# schematic.net
KiCad netlist of a schematic drawn in EasyEDA
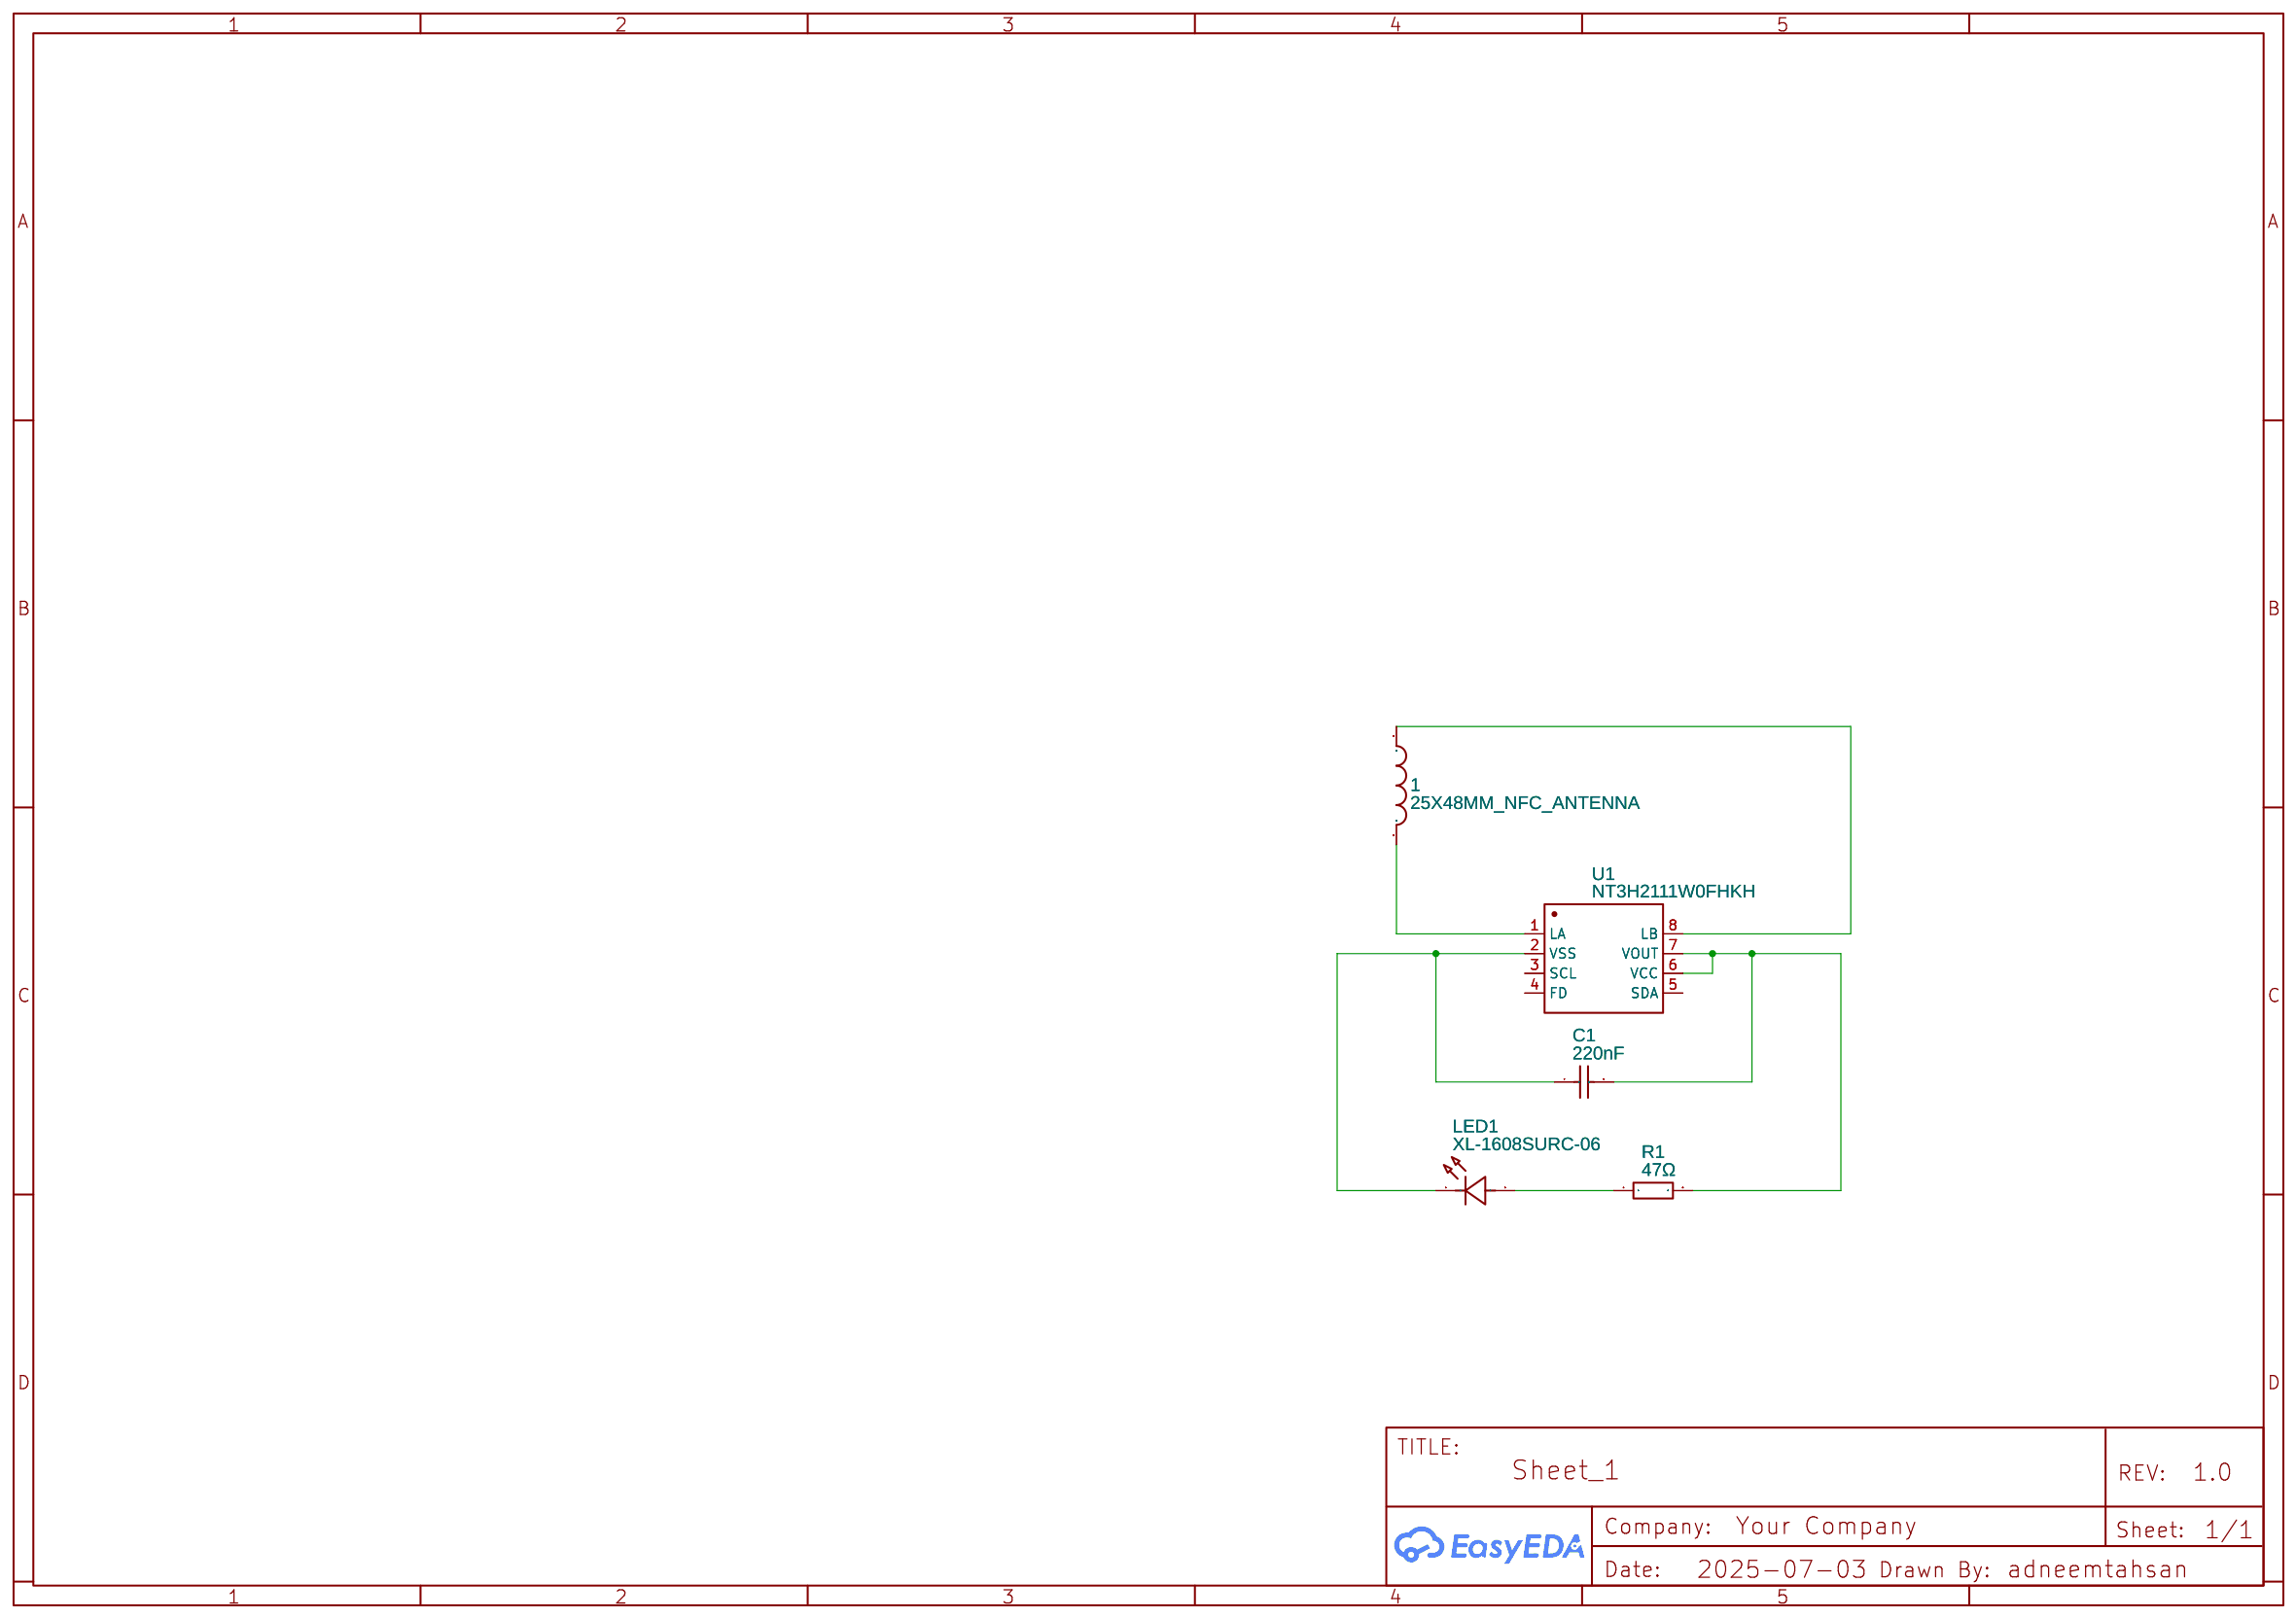
[diagram p0: schematic sheet]

(export (version "E")
  (design (tool "Eeschema 10.0.6"))
  (components
    (comp (ref "1") (value "25X48MM_NFC_ANTENNA") (libsource (lib "") (part "25X48MM_NFC_ANTENNA")))
    (comp (ref "C1")
      (value "220nF")
      (fields
        (field (name "Manufacturer Part") "CL10B224KA8NNNC")
        (field (name "Manufacturer") "SAMSUNG(三星)")
      )
      (libsource (lib "") (part "CL10B224KA8NNNC"))
    )
    (comp (ref "LED1")
      (value "XL-1608SURC-06")
      (fields (field (name "Manufacturer") "XINGLIGHT(成兴光)"))
      (libsource (lib "") (part "XL-1608SURC-06"))
    )
    (comp (ref "R1")
      (value "47Ω")
      (fields
        (field (name "Manufacturer Part") "0603WAF470JT5E")
        (field (name "Manufacturer") "UNI-ROYAL(厚声)")
      )
      (libsource (lib "") (part "0603WAF470JT5E"))
    )
    (comp (ref "U1")
      (value "NT3H2111W0FHKH")
      (fields (field (name "Manufacturer") "NXP(恩智浦)"))
      (libsource (lib "") (part "NT3H2111W0FHKH"))
    )
  )
  (nets
    (net (code "1") (name "Net-(LED1-A)") (class "Default")
      (node (ref "LED1") (pin "2") (pinfunction "A_2") (pintype "unspecified"))
      (node (ref "R1") (pin "1") (pinfunction "1_1") (pintype "input"))
    )
    (net (code "2") (name "Net-(LED1-K)") (class "Default")
      (node (ref "C1") (pin "1") (pinfunction "1_1") (pintype "input"))
      (node (ref "LED1") (pin "1") (pinfunction "K_1") (pintype "unspecified"))
      (node (ref "U1") (pin "2") (pinfunction "VSS_2") (pintype "unspecified"))
    )
    (net (code "3") (name "Net-(U1-LA)") (class "Default")
      (node (ref "1") (pin "P$2") (pinfunction "P$2_P$2") (pintype "bidirectional"))
      (node (ref "U1") (pin "1") (pinfunction "LA_1") (pintype "unspecified"))
    )
    (net (code "4") (name "Net-(U1-LB)") (class "Default")
      (node (ref "1") (pin "P$1") (pinfunction "P$1_P$1") (pintype "bidirectional"))
      (node (ref "U1") (pin "8") (pinfunction "LB_8") (pintype "unspecified"))
    )
    (net (code "5") (name "Net-(U1-VCC)") (class "Default")
      (node (ref "C1") (pin "2") (pinfunction "2_2") (pintype "input"))
      (node (ref "R1") (pin "2") (pinfunction "2_2") (pintype "input"))
      (node (ref "U1") (pin "6") (pinfunction "VCC_6") (pintype "unspecified"))
      (node (ref "U1") (pin "7") (pinfunction "VOUT_7") (pintype "unspecified"))
    )
    (net (code "6") (name "unconnected-(U1-FD-Pad4)") (class "Default")
      (node (ref "U1") (pin "4") (pinfunction "FD_4") (pintype "unspecified"))
    )
    (net (code "7") (name "unconnected-(U1-SCL-Pad3)") (class "Default")
      (node (ref "U1") (pin "3") (pinfunction "SCL_3") (pintype "unspecified"))
    )
    (net (code "8") (name "unconnected-(U1-SDA-Pad5)") (class "Default")
      (node (ref "U1") (pin "5") (pinfunction "SDA_5") (pintype "unspecified"))
    )
  )
)
